# 05_CONNECTOR_OUT.net
KiCad netlist of a schematic drawn in Altium Designer
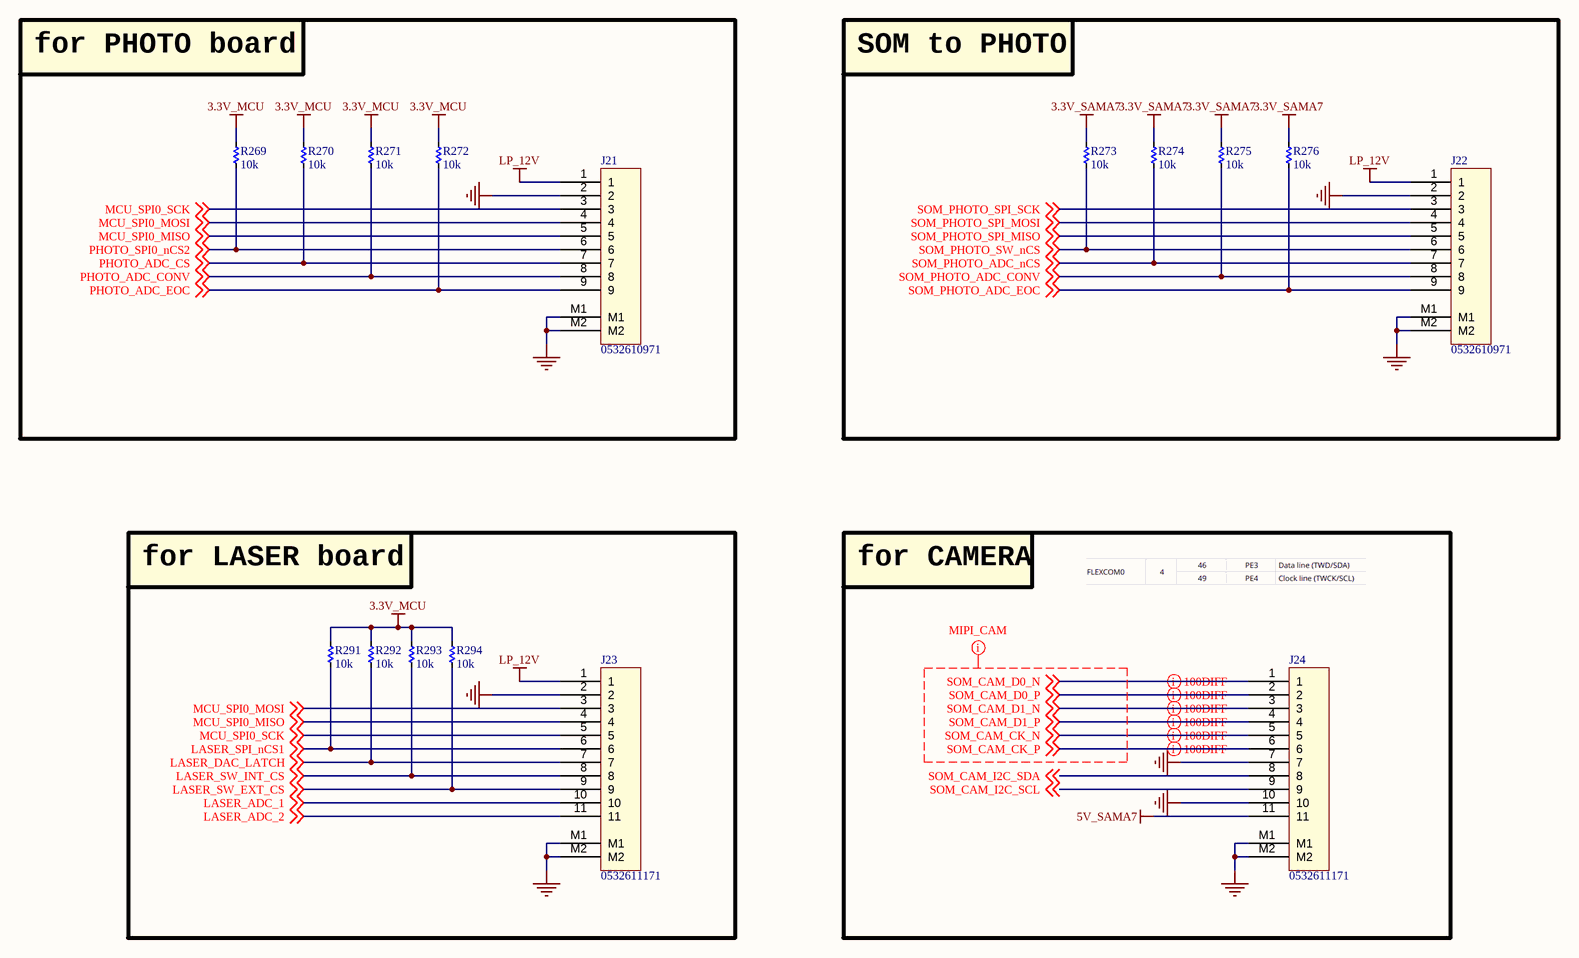
[diagram p0: 05_CONNECTOR_OUT.SchDoc]

(export (version "E")
  (design (tool "Eeschema 10.0.6"))
  (components
    (comp (ref "J21")
      (value "0532610971")
      (footprint "MOLEX_0532610971")
      (libsource (lib "LABLIB") (part "Header 9x1_2M"))
    )
    (comp (ref "J22")
      (value "0532610971")
      (footprint "MOLEX_0532610971")
      (libsource (lib "LABLIB") (part "Header 9x1_2M"))
    )
    (comp (ref "J23")
      (value "0532611171")
      (footprint "MOLEX_0532611171")
      (libsource (lib "LABLIB") (part "Header 11x1_2M"))
    )
    (comp (ref "J24")
      (value "0532611171")
      (footprint "MOLEX_0532611171")
      (libsource (lib "LABLIB") (part "Header 11x1_2M"))
    )
    (comp (ref "R269")
      (value "10k")
      (footprint "RES_C_1005x30_L")
      (description "RES")
      (libsource (lib "LABLIB") (part "_RES_B_2"))
    )
    (comp (ref "R270")
      (value "10k")
      (footprint "RES_C_1005x30_L")
      (description "RES")
      (libsource (lib "LABLIB") (part "_RES_B_2"))
    )
    (comp (ref "R271")
      (value "10k")
      (footprint "RES_C_1005x30_L")
      (description "RES")
      (libsource (lib "LABLIB") (part "_RES_B_2"))
    )
    (comp (ref "R272")
      (value "10k")
      (footprint "RES_C_1005x30_L")
      (description "RES")
      (libsource (lib "LABLIB") (part "_RES_B_2"))
    )
    (comp (ref "R273")
      (value "10k")
      (footprint "RES_C_1005x30_L")
      (description "RES")
      (libsource (lib "LABLIB") (part "_RES_B_2"))
    )
    (comp (ref "R274")
      (value "10k")
      (footprint "RES_C_1005x30_L")
      (description "RES")
      (libsource (lib "LABLIB") (part "_RES_B_2"))
    )
    (comp (ref "R275")
      (value "10k")
      (footprint "RES_C_1005x30_L")
      (description "RES")
      (libsource (lib "LABLIB") (part "_RES_B_2"))
    )
    (comp (ref "R276")
      (value "10k")
      (footprint "RES_C_1005x30_L")
      (description "RES")
      (libsource (lib "LABLIB") (part "_RES_B_2"))
    )
    (comp (ref "R291")
      (value "10k")
      (footprint "RES_C_1005x30_L")
      (description "RES")
      (libsource (lib "LABLIB") (part "_RES_B_2"))
    )
    (comp (ref "R292")
      (value "10k")
      (footprint "RES_C_1005x30_L")
      (description "RES")
      (libsource (lib "LABLIB") (part "_RES_B_2"))
    )
    (comp (ref "R293")
      (value "10k")
      (footprint "RES_C_1005x30_L")
      (description "RES")
      (libsource (lib "LABLIB") (part "_RES_B_2"))
    )
    (comp (ref "R294")
      (value "10k")
      (footprint "RES_C_1005x30_L")
      (description "RES")
      (libsource (lib "LABLIB") (part "_RES_B_2"))
    )
  )
  (nets
    (net (code "1") (name "3.3V_MCU") (class "Default")
      (node (ref "R269") (pin "1") (pinfunction "1_1") (pintype "passive"))
      (node (ref "R270") (pin "1") (pinfunction "1_1") (pintype "passive"))
      (node (ref "R271") (pin "1") (pinfunction "1_1") (pintype "passive"))
      (node (ref "R272") (pin "1") (pinfunction "1_1") (pintype "passive"))
      (node (ref "R291") (pin "1") (pinfunction "1_1") (pintype "passive"))
      (node (ref "R292") (pin "1") (pinfunction "1_1") (pintype "passive"))
      (node (ref "R293") (pin "1") (pinfunction "1_1") (pintype "passive"))
      (node (ref "R294") (pin "1") (pinfunction "1_1") (pintype "passive"))
    )
    (net (code "2") (name "3.3V_SAMA7") (class "Default")
      (node (ref "R273") (pin "1") (pinfunction "1_1") (pintype "passive"))
      (node (ref "R274") (pin "1") (pinfunction "1_1") (pintype "passive"))
      (node (ref "R275") (pin "1") (pinfunction "1_1") (pintype "passive"))
      (node (ref "R276") (pin "1") (pinfunction "1_1") (pintype "passive"))
    )
    (net (code "3") (name "5V_SAMA7") (class "Default")
      (node (ref "J24") (pin "11") (pinfunction "11_11") (pintype "passive"))
    )
    (net (code "4") (name "GND") (class "Default")
      (node (ref "J21") (pin "2") (pinfunction "2_2") (pintype "passive"))
      (node (ref "J21") (pin "M1") (pinfunction "M1_M1") (pintype "passive"))
      (node (ref "J21") (pin "M2") (pinfunction "M2_M2") (pintype "passive"))
      (node (ref "J22") (pin "2") (pinfunction "2_2") (pintype "passive"))
      (node (ref "J22") (pin "M1") (pinfunction "M1_M1") (pintype "passive"))
      (node (ref "J22") (pin "M2") (pinfunction "M2_M2") (pintype "passive"))
      (node (ref "J23") (pin "2") (pinfunction "2_2") (pintype "passive"))
      (node (ref "J23") (pin "M1") (pinfunction "M1_M1") (pintype "passive"))
      (node (ref "J23") (pin "M2") (pinfunction "M2_M2") (pintype "passive"))
      (node (ref "J24") (pin "10") (pinfunction "10_10") (pintype "passive"))
      (node (ref "J24") (pin "7") (pinfunction "7_7") (pintype "passive"))
      (node (ref "J24") (pin "M1") (pinfunction "M1_M1") (pintype "passive"))
      (node (ref "J24") (pin "M2") (pinfunction "M2_M2") (pintype "passive"))
    )
    (net (code "5") (name "LASER_ADC_1") (class "Default")
      (node (ref "J23") (pin "10") (pinfunction "10_10") (pintype "passive"))
    )
    (net (code "6") (name "LASER_ADC_2") (class "Default")
      (node (ref "J23") (pin "11") (pinfunction "11_11") (pintype "passive"))
    )
    (net (code "7") (name "LASER_DAC_LATCH") (class "Default")
      (node (ref "J23") (pin "7") (pinfunction "7_7") (pintype "passive"))
      (node (ref "R292") (pin "2") (pinfunction "2_2") (pintype "passive"))
    )
    (net (code "8") (name "LASER_SPI_nCS1") (class "Default")
      (node (ref "J23") (pin "6") (pinfunction "6_6") (pintype "passive"))
      (node (ref "R291") (pin "2") (pinfunction "2_2") (pintype "passive"))
    )
    (net (code "9") (name "LASER_SW_EXT_CS") (class "Default")
      (node (ref "J23") (pin "9") (pinfunction "9_9") (pintype "passive"))
      (node (ref "R294") (pin "2") (pinfunction "2_2") (pintype "passive"))
    )
    (net (code "10") (name "LASER_SW_INT_CS") (class "Default")
      (node (ref "J23") (pin "8") (pinfunction "8_8") (pintype "passive"))
      (node (ref "R293") (pin "2") (pinfunction "2_2") (pintype "passive"))
    )
    (net (code "11") (name "LP_12V") (class "Default")
      (node (ref "J21") (pin "1") (pinfunction "1_1") (pintype "passive"))
      (node (ref "J22") (pin "1") (pinfunction "1_1") (pintype "passive"))
      (node (ref "J23") (pin "1") (pinfunction "1_1") (pintype "passive"))
    )
    (net (code "12") (name "MCU_SPI0_MISO") (class "Default")
      (node (ref "J21") (pin "5") (pinfunction "5_5") (pintype "passive"))
      (node (ref "J23") (pin "4") (pinfunction "4_4") (pintype "passive"))
    )
    (net (code "13") (name "MCU_SPI0_MOSI") (class "Default")
      (node (ref "J21") (pin "4") (pinfunction "4_4") (pintype "passive"))
      (node (ref "J23") (pin "3") (pinfunction "3_3") (pintype "passive"))
    )
    (net (code "14") (name "MCU_SPI0_SCK") (class "Default")
      (node (ref "J21") (pin "3") (pinfunction "3_3") (pintype "passive"))
      (node (ref "J23") (pin "5") (pinfunction "5_5") (pintype "passive"))
    )
    (net (code "15") (name "PHOTO_ADC_CONV") (class "Default")
      (node (ref "J21") (pin "8") (pinfunction "8_8") (pintype "passive"))
      (node (ref "R271") (pin "2") (pinfunction "2_2") (pintype "passive"))
    )
    (net (code "16") (name "PHOTO_ADC_CS") (class "Default")
      (node (ref "J21") (pin "7") (pinfunction "7_7") (pintype "passive"))
      (node (ref "R270") (pin "2") (pinfunction "2_2") (pintype "passive"))
    )
    (net (code "17") (name "PHOTO_ADC_EOC") (class "Default")
      (node (ref "J21") (pin "9") (pinfunction "9_9") (pintype "passive"))
      (node (ref "R272") (pin "2") (pinfunction "2_2") (pintype "passive"))
    )
    (net (code "18") (name "PHOTO_SPI0_nCS2") (class "Default")
      (node (ref "J21") (pin "6") (pinfunction "6_6") (pintype "passive"))
      (node (ref "R269") (pin "2") (pinfunction "2_2") (pintype "passive"))
    )
    (net (code "19") (name "SOM_CAM_CK_N") (class "Default")
      (node (ref "J24") (pin "5") (pinfunction "5_5") (pintype "passive"))
    )
    (net (code "20") (name "SOM_CAM_CK_P") (class "Default")
      (node (ref "J24") (pin "6") (pinfunction "6_6") (pintype "passive"))
    )
    (net (code "21") (name "SOM_CAM_D0_N") (class "Default")
      (node (ref "J24") (pin "1") (pinfunction "1_1") (pintype "passive"))
    )
    (net (code "22") (name "SOM_CAM_D0_P") (class "Default")
      (node (ref "J24") (pin "2") (pinfunction "2_2") (pintype "passive"))
    )
    (net (code "23") (name "SOM_CAM_D1_N") (class "Default")
      (node (ref "J24") (pin "3") (pinfunction "3_3") (pintype "passive"))
    )
    (net (code "24") (name "SOM_CAM_D1_P") (class "Default")
      (node (ref "J24") (pin "4") (pinfunction "4_4") (pintype "passive"))
    )
    (net (code "25") (name "SOM_CAM_I2C_SCL") (class "Default")
      (node (ref "J24") (pin "9") (pinfunction "9_9") (pintype "passive"))
    )
    (net (code "26") (name "SOM_CAM_I2C_SDA") (class "Default")
      (node (ref "J24") (pin "8") (pinfunction "8_8") (pintype "passive"))
    )
    (net (code "27") (name "SOM_PHOTO_ADC_CONV") (class "Default")
      (node (ref "J22") (pin "8") (pinfunction "8_8") (pintype "passive"))
      (node (ref "R275") (pin "2") (pinfunction "2_2") (pintype "passive"))
    )
    (net (code "28") (name "SOM_PHOTO_ADC_EOC") (class "Default")
      (node (ref "J22") (pin "9") (pinfunction "9_9") (pintype "passive"))
      (node (ref "R276") (pin "2") (pinfunction "2_2") (pintype "passive"))
    )
    (net (code "29") (name "SOM_PHOTO_ADC_nCS") (class "Default")
      (node (ref "J22") (pin "7") (pinfunction "7_7") (pintype "passive"))
      (node (ref "R274") (pin "2") (pinfunction "2_2") (pintype "passive"))
    )
    (net (code "30") (name "SOM_PHOTO_SPI_MISO") (class "Default")
      (node (ref "J22") (pin "5") (pinfunction "5_5") (pintype "passive"))
    )
    (net (code "31") (name "SOM_PHOTO_SPI_MOSI") (class "Default")
      (node (ref "J22") (pin "4") (pinfunction "4_4") (pintype "passive"))
    )
    (net (code "32") (name "SOM_PHOTO_SPI_SCK") (class "Default")
      (node (ref "J22") (pin "3") (pinfunction "3_3") (pintype "passive"))
    )
    (net (code "33") (name "SOM_PHOTO_SW_nCS") (class "Default")
      (node (ref "J22") (pin "6") (pinfunction "6_6") (pintype "passive"))
      (node (ref "R273") (pin "2") (pinfunction "2_2") (pintype "passive"))
    )
  )
)
